# rs485.net
KiCad netlist of a schematic drawn in Altium Designer
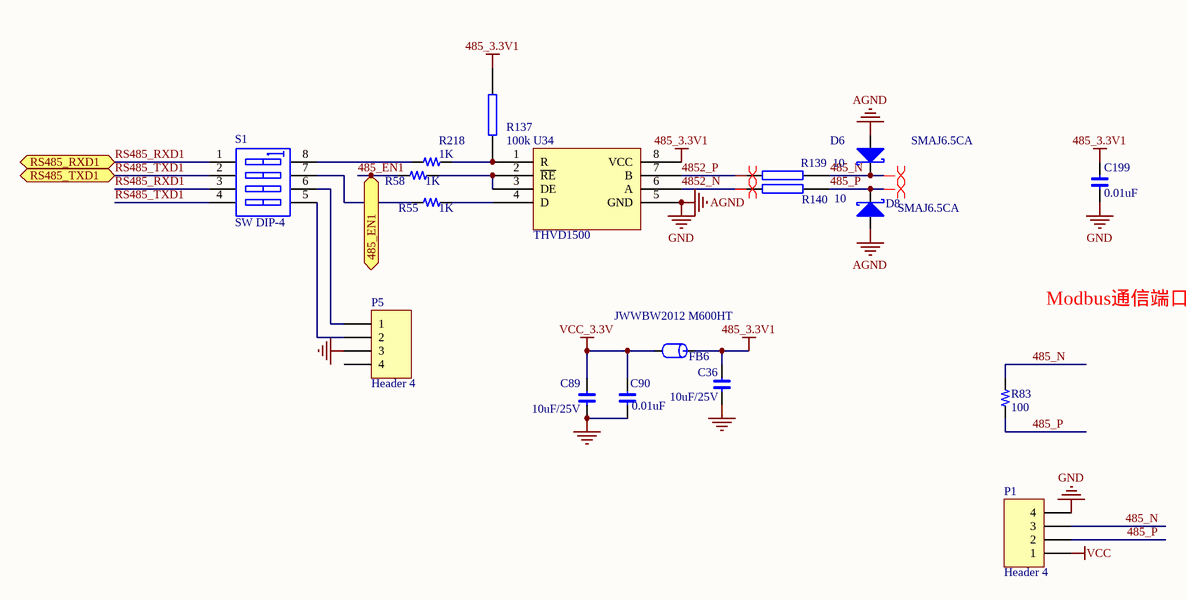
[diagram p0: rs485.SchDoc]

(export (version "E")
  (design (tool "Eeschema 10.0.6"))
  (components
    (comp (ref "C36")
      (value "10uF/25V")
      (footprint "0603C")
      (description "C")
      (libsource (lib "Schlib_20110825") (part "C"))
    )
    (comp (ref "C89")
      (value "10uF/25V")
      (footprint "0603C")
      (description "C")
      (libsource (lib "Schlib_20110825") (part "C"))
    )
    (comp (ref "C90")
      (value "0.01uF")
      (footprint "0603C")
      (description "C")
      (libsource (lib "Schlib_20110825") (part "C"))
    )
    (comp (ref "C199")
      (value "0.01uF")
      (footprint "0603C")
      (description "C")
      (libsource (lib "Schlib_20110825") (part "C"))
    )
    (comp (ref "D6")
      (value "SMAJ6.5CA")
      (footprint "SMA")
      (description "Schottky Diode")
      (libsource (lib "*") (part "DIODE S"))
    )
    (comp (ref "D8")
      (value "SMAJ6.5CA")
      (footprint "SMA")
      (description "Schottky Diode")
      (libsource (lib "*") (part "DIODE S"))
    )
    (comp (ref "FB6")
      (value "JWWBW2012 M600HT")
      (footprint "0805CZ")
      (libsource (lib "Schlib_20110825") (part "FB"))
    )
    (comp (ref "P1")
      (value "Header 4")
      (footprint "4X2.54MMZ")
      (description "Header, 4-Pin")
      (fields (field (name "PUBLISHER") "Altium Limited"))
      (libsource (lib "") (part "Header 4_1"))
    )
    (comp (ref "P5")
      (value "Header 4")
      (footprint "4X2.54MMZ")
      (description "Header, 4-Pin")
      (fields (field (name "PUBLISHER") "Altium Limited"))
      (libsource (lib "Miscellaneous Connectors") (part "Header 4"))
    )
    (comp (ref "R55") (value "1K") (footprint "0603R") (description "R") (libsource (lib "JRJ_1") (part "R")))
    (comp (ref "R58") (value "1K") (footprint "0603R") (description "R") (libsource (lib "JRJ_1") (part "R")))
    (comp (ref "R83")
      (value "100")
      (footprint "0603R")
      (description "R")
      (libsource (lib "JRJ_1") (part "R"))
    )
    (comp (ref "R137") (value "100k") (footprint "0603R") (libsource (lib "*") (part "RES2")))
    (comp (ref "R139") (value "10") (footprint "1206R") (libsource (lib "*") (part "RES2")))
    (comp (ref "R140") (value "10") (footprint "1206R") (libsource (lib "*") (part "RES2")))
    (comp (ref "R218")
      (value "1K")
      (footprint "0603R")
      (description "R")
      (libsource (lib "JRJ_1") (part "R"))
    )
    (comp (ref "S1")
      (value "SW DIP-4")
      (footprint "SW_SMT_8")
      (description "DIP Switch, 4 Position, SPST")
      (fields (field (name "PUBLISHER") "Altium Limited"))
      (libsource (lib "Miscellaneous Devices") (part "SW DIP-4"))
    )
    (comp (ref "U34") (value "THVD1500") (footprint "so-8") (libsource (lib "Schlib1") (part "SN65HVD06D")))
  )
  (nets
    (net (code "1") (name "/485_EN1") (class "Default") (node (ref "R58") (pin "2") (pintype "passive")))
    (net (code "2") (name "/485_N") (class "Default")
      (node (ref "D6") (pin "2") (pinfunction "K_2") (pintype "passive"))
      (node (ref "P1") (pin "3") (pinfunction "3_3") (pintype "passive"))
      (node (ref "R139") (pin "1") (pinfunction "1_1") (pintype "passive"))
      (node (ref "R83") (pin "2") (pintype "passive"))
    )
    (net (code "3") (name "/485_P") (class "Default")
      (node (ref "D8") (pin "2") (pinfunction "K_2") (pintype "passive"))
      (node (ref "P1") (pin "2") (pinfunction "2_2") (pintype "passive"))
      (node (ref "R140") (pin "1") (pinfunction "1_1") (pintype "passive"))
      (node (ref "R83") (pin "1") (pintype "passive"))
    )
    (net (code "4") (name "/4852_N") (class "Default")
      (node (ref "R140") (pin "2") (pinfunction "2_2") (pintype "passive"))
      (node (ref "U34") (pin "6") (pinfunction "A_6") (pintype "passive"))
    )
    (net (code "5") (name "/4852_P") (class "Default")
      (node (ref "R139") (pin "2") (pinfunction "2_2") (pintype "passive"))
      (node (ref "U34") (pin "7") (pinfunction "B_7") (pintype "passive"))
    )
    (net (code "6") (name "/RS485_RXD1") (class "Default")
      (node (ref "S1") (pin "1") (pinfunction "A1_1") (pintype "passive"))
      (node (ref "S1") (pin "3") (pinfunction "A3_3") (pintype "passive"))
    )
    (net (code "7") (name "/RS485_TXD1") (class "Default")
      (node (ref "S1") (pin "2") (pinfunction "A2_2") (pintype "passive"))
      (node (ref "S1") (pin "4") (pinfunction "A4_4") (pintype "passive"))
    )
    (net (code "8") (name "485_3.3V1") (class "Default")
      (node (ref "C199") (pin "2") (pintype "passive"))
      (node (ref "C36") (pin "2") (pintype "passive"))
      (node (ref "FB6") (pin "1") (pintype "passive"))
      (node (ref "R137") (pin "2") (pinfunction "2_2") (pintype "passive"))
      (node (ref "U34") (pin "8") (pinfunction "VCC_8") (pintype "passive"))
    )
    (net (code "9") (name "AGND") (class "Default")
      (node (ref "C199") (pin "1") (pintype "passive"))
      (node (ref "C36") (pin "1") (pintype "passive"))
      (node (ref "C89") (pin "1") (pintype "passive"))
      (node (ref "C90") (pin "1") (pintype "passive"))
      (node (ref "D6") (pin "1") (pinfunction "A_1") (pintype "passive"))
      (node (ref "D8") (pin "1") (pinfunction "A_1") (pintype "passive"))
      (node (ref "P1") (pin "4") (pinfunction "4_4") (pintype "passive"))
      (node (ref "P5") (pin "3") (pinfunction "3_3") (pintype "passive"))
      (node (ref "U34") (pin "5") (pinfunction "GND_5") (pintype "passive"))
    )
    (net (code "10") (name "Net-(S1-B1)") (class "Default")
      (node (ref "R218") (pin "2") (pintype "passive"))
      (node (ref "S1") (pin "8") (pinfunction "B1_8") (pintype "passive"))
    )
    (net (code "11") (name "Net-(S1-B2)") (class "Default")
      (node (ref "R55") (pin "2") (pintype "passive"))
      (node (ref "S1") (pin "7") (pinfunction "B2_7") (pintype "passive"))
    )
    (net (code "12") (name "Net-(S1-B3)") (class "Default")
      (node (ref "P5") (pin "1") (pinfunction "1_1") (pintype "passive"))
      (node (ref "S1") (pin "6") (pinfunction "B3_6") (pintype "passive"))
    )
    (net (code "13") (name "Net-(S1-B4)") (class "Default")
      (node (ref "P5") (pin "2") (pinfunction "2_2") (pintype "passive"))
      (node (ref "S1") (pin "5") (pinfunction "B4_5") (pintype "passive"))
    )
    (net (code "14") (name "Net-(U34-D)") (class "Default")
      (node (ref "R55") (pin "1") (pintype "passive"))
      (node (ref "U34") (pin "4") (pinfunction "D_4") (pintype "passive"))
    )
    (net (code "15") (name "Net-(U34-DE)") (class "Default")
      (node (ref "R58") (pin "1") (pintype "passive"))
      (node (ref "U34") (pin "2") (pinfunction "~{RE}_2") (pintype "passive"))
      (node (ref "U34") (pin "3") (pinfunction "DE_3") (pintype "passive"))
    )
    (net (code "16") (name "Net-(U34-R)") (class "Default")
      (node (ref "R137") (pin "1") (pinfunction "1_1") (pintype "passive"))
      (node (ref "R218") (pin "1") (pintype "passive"))
      (node (ref "U34") (pin "1") (pinfunction "R_1") (pintype "passive"))
    )
    (net (code "17") (name "VCC") (class "Default")
      (node (ref "P1") (pin "1") (pinfunction "1_1") (pintype "passive"))
    )
    (net (code "18") (name "VCC_3.3V") (class "Default")
      (node (ref "C89") (pin "2") (pintype "passive"))
      (node (ref "C90") (pin "2") (pintype "passive"))
      (node (ref "FB6") (pin "2") (pintype "passive"))
    )
    (net (code "19") (name "unconnected-(P5-Pad4)") (class "Default")
      (node (ref "P5") (pin "4") (pinfunction "4_4") (pintype "passive"))
    )
  )
)
